# ds3231.net
KiCad netlist of a schematic drawn in EAGLE
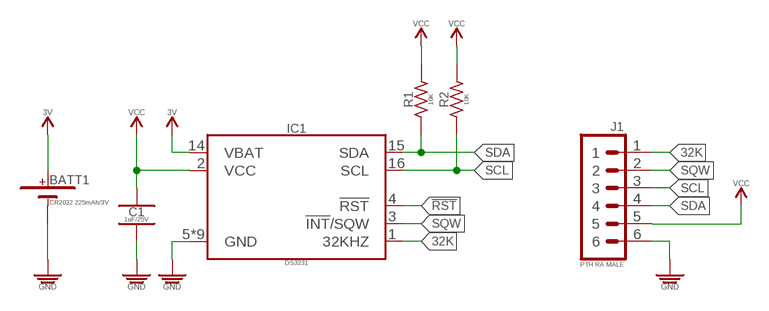
[diagram p0: schematic, sheet 1]

(export (version "E")
  (design (tool "Eeschema 10.0.6"))
  (components
    (comp (ref "BATT1")
      (value "CR2032 225mAh/3V")
      (footprint "eagle-import:CR-2032")
      (fields (field (name "MFR") "Panasonic - BSG") (field (name "MPN") "CR2032"))
      (libsource (lib "eagle-import") (part "BATTERY_COIN-CELL_SMD_3V_20MM"))
    )
    (comp (ref "C1")
      (value "1uF/25V")
      (footprint "eagle-import:CAPC1005X55_SMD-0402")
      (fields (field (name "MFR") "TDK Corporation") (field (name "MPN") "CGB2A1X5R1E105K033BC"))
      (libsource (lib "eagle-import") (part "1UF_CER_SMD-0402_25V-10%"))
    )
    (comp (ref "IC1")
      (value "DS3231")
      (footprint "eagle-import:SOIC127P1032X265-16")
      (fields (field (name "MFR") "Maxim Integrated") (field (name "MPN") "DS3231S#T&R"))
      (libsource (lib "eagle-import") (part "DS3231_DS3231_RTC_CLK_I2C_SOIC-16"))
    )
    (comp (ref "J1")
      (value "PTH RA MALE")
      (footprint "eagle-import:HDRRA6W64P254_1X6_1524X254X254B")
      (fields (field (name "MFR") "Sullins Connector Solutions") (field (name "MPN") "PEC06SBAN"))
      (libsource (lib "eagle-import") (part "1X06PTH_RA_MALE_2.54MM"))
    )
    (comp (ref "R1")
      (value "10K")
      (footprint "eagle-import:RESC1005X35_SMD-0402")
      (fields (field (name "MFR") "Yageo") (field (name "MPN") "RC0402JR-0710KP"))
      (libsource (lib "eagle-import") (part "10KΩ_SMD-0402_1/16W-5%"))
    )
    (comp (ref "R2")
      (value "10K")
      (footprint "eagle-import:RESC1005X35_SMD-0402")
      (fields (field (name "MFR") "Yageo") (field (name "MPN") "RC0402JR-0710KP"))
      (libsource (lib "eagle-import") (part "10KΩ_SMD-0402_1/16W-5%"))
    )
  )
  (nets
    (net (code "1") (name "/~{RST}") (class "Default")
      (node (ref "IC1") (pin "4") (pinfunction "~{RST}_4") (pintype "bidirectional"))
    )
    (net (code "2") (name "3V") (class "Default")
      (node (ref "BATT1") (pin "+_1") (pinfunction "+_+_1") (pintype "passive"))
      (node (ref "BATT1") (pin "+_2") (pinfunction "+_+_2") (pintype "passive"))
      (node (ref "IC1") (pin "14") (pinfunction "VBAT_14") (pintype "bidirectional"))
    )
    (net (code "3") (name "32K") (class "Default")
      (node (ref "IC1") (pin "1") (pinfunction "32KHZ_1") (pintype "bidirectional"))
      (node (ref "J1") (pin "1") (pinfunction "1_1") (pintype "passive"))
    )
    (net (code "4") (name "GND") (class "Default")
      (node (ref "BATT1") (pin "-") (pinfunction "-_-") (pintype "passive"))
      (node (ref "C1") (pin "2") (pinfunction "2_2") (pintype "passive"))
      (node (ref "IC1") (pin "10") (pinfunction "GND_10") (pintype "bidirectional"))
      (node (ref "IC1") (pin "11") (pinfunction "GND_11") (pintype "bidirectional"))
      (node (ref "IC1") (pin "12") (pinfunction "GND_12") (pintype "bidirectional"))
      (node (ref "IC1") (pin "13") (pinfunction "GND_13") (pintype "bidirectional"))
      (node (ref "IC1") (pin "5") (pinfunction "GND_5") (pintype "bidirectional"))
      (node (ref "IC1") (pin "6") (pinfunction "GND_6") (pintype "bidirectional"))
      (node (ref "IC1") (pin "7") (pinfunction "GND_7") (pintype "bidirectional"))
      (node (ref "IC1") (pin "8") (pinfunction "GND_8") (pintype "bidirectional"))
      (node (ref "IC1") (pin "9") (pinfunction "GND_9") (pintype "bidirectional"))
      (node (ref "J1") (pin "6") (pinfunction "6_6") (pintype "passive"))
    )
    (net (code "5") (name "SCL") (class "Default")
      (node (ref "IC1") (pin "16") (pinfunction "SCL_16") (pintype "bidirectional"))
      (node (ref "J1") (pin "3") (pinfunction "3_3") (pintype "passive"))
      (node (ref "R2") (pin "1") (pinfunction "1_1") (pintype "passive"))
    )
    (net (code "6") (name "SDA") (class "Default")
      (node (ref "IC1") (pin "15") (pinfunction "SDA_15") (pintype "bidirectional"))
      (node (ref "J1") (pin "4") (pinfunction "4_4") (pintype "passive"))
      (node (ref "R1") (pin "1") (pinfunction "1_1") (pintype "passive"))
    )
    (net (code "7") (name "SQW") (class "Default")
      (node (ref "IC1") (pin "3") (pinfunction "~{INT}/SQW_3") (pintype "bidirectional"))
      (node (ref "J1") (pin "2") (pinfunction "2_2") (pintype "passive"))
    )
    (net (code "8") (name "VCC") (class "Default")
      (node (ref "C1") (pin "1") (pinfunction "1_1") (pintype "passive"))
      (node (ref "IC1") (pin "2") (pinfunction "VCC_2") (pintype "bidirectional"))
      (node (ref "J1") (pin "5") (pinfunction "5_5") (pintype "passive"))
      (node (ref "R1") (pin "2") (pinfunction "2_2") (pintype "passive"))
      (node (ref "R2") (pin "2") (pinfunction "2_2") (pintype "passive"))
    )
  )
)
